# Sensoray_Breakout.net
KiCad netlist of a schematic drawn in EAGLE
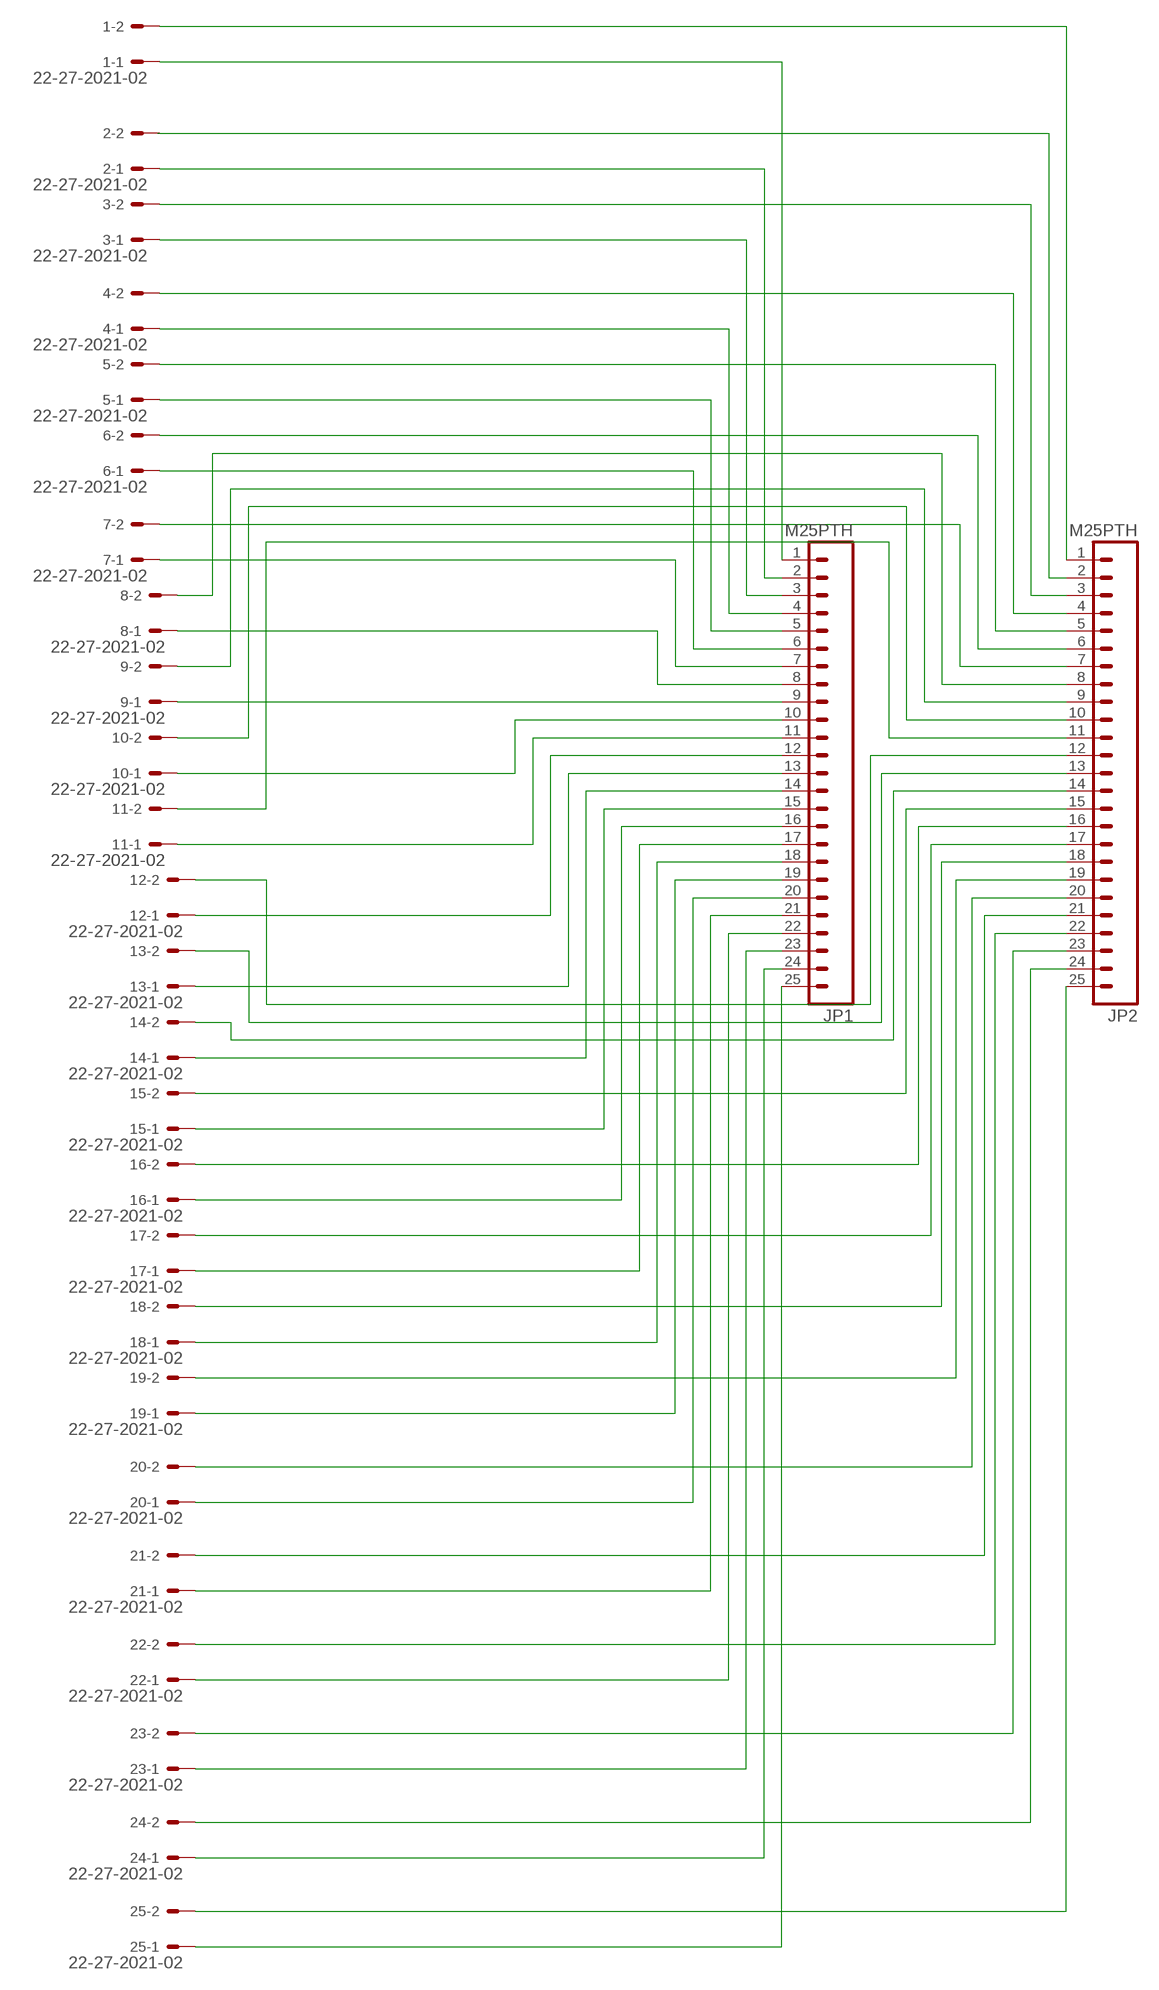
[diagram p0: schematic, sheet 1]

(export (version "E")
  (design (tool "Eeschema 10.0.6"))
  (components
    (comp (ref "1")
      (value "22-27-2021-02")
      (footprint "eagle-import:6410-02")
      (libsource (lib "eagle-import") (part "22-?-0227-2021"))
    )
    (comp (ref "2")
      (value "22-27-2021-02")
      (footprint "eagle-import:6410-02")
      (libsource (lib "eagle-import") (part "22-?-0227-2021"))
    )
    (comp (ref "3")
      (value "22-27-2021-02")
      (footprint "eagle-import:6410-02")
      (libsource (lib "eagle-import") (part "22-?-0227-2021"))
    )
    (comp (ref "4")
      (value "22-27-2021-02")
      (footprint "eagle-import:6410-02")
      (libsource (lib "eagle-import") (part "22-?-0227-2021"))
    )
    (comp (ref "5")
      (value "22-27-2021-02")
      (footprint "eagle-import:6410-02")
      (libsource (lib "eagle-import") (part "22-?-0227-2021"))
    )
    (comp (ref "6")
      (value "22-27-2021-02")
      (footprint "eagle-import:6410-02")
      (libsource (lib "eagle-import") (part "22-?-0227-2021"))
    )
    (comp (ref "7")
      (value "22-27-2021-02")
      (footprint "eagle-import:6410-02")
      (libsource (lib "eagle-import") (part "22-?-0227-2021"))
    )
    (comp (ref "8")
      (value "22-27-2021-02")
      (footprint "eagle-import:6410-02")
      (libsource (lib "eagle-import") (part "22-?-0227-2021"))
    )
    (comp (ref "9")
      (value "22-27-2021-02")
      (footprint "eagle-import:6410-02")
      (libsource (lib "eagle-import") (part "22-?-0227-2021"))
    )
    (comp (ref "10")
      (value "22-27-2021-02")
      (footprint "eagle-import:6410-02")
      (libsource (lib "eagle-import") (part "22-?-0227-2021"))
    )
    (comp (ref "11")
      (value "22-27-2021-02")
      (footprint "eagle-import:6410-02")
      (libsource (lib "eagle-import") (part "22-?-0227-2021"))
    )
    (comp (ref "12")
      (value "22-27-2021-02")
      (footprint "eagle-import:6410-02")
      (libsource (lib "eagle-import") (part "22-?-0227-2021"))
    )
    (comp (ref "13")
      (value "22-27-2021-02")
      (footprint "eagle-import:6410-02")
      (libsource (lib "eagle-import") (part "22-?-0227-2021"))
    )
    (comp (ref "14")
      (value "22-27-2021-02")
      (footprint "eagle-import:6410-02")
      (libsource (lib "eagle-import") (part "22-?-0227-2021"))
    )
    (comp (ref "15")
      (value "22-27-2021-02")
      (footprint "eagle-import:6410-02")
      (libsource (lib "eagle-import") (part "22-?-0227-2021"))
    )
    (comp (ref "16")
      (value "22-27-2021-02")
      (footprint "eagle-import:6410-02")
      (libsource (lib "eagle-import") (part "22-?-0227-2021"))
    )
    (comp (ref "17")
      (value "22-27-2021-02")
      (footprint "eagle-import:6410-02")
      (libsource (lib "eagle-import") (part "22-?-0227-2021"))
    )
    (comp (ref "18")
      (value "22-27-2021-02")
      (footprint "eagle-import:6410-02")
      (libsource (lib "eagle-import") (part "22-?-0227-2021"))
    )
    (comp (ref "19")
      (value "22-27-2021-02")
      (footprint "eagle-import:6410-02")
      (libsource (lib "eagle-import") (part "22-?-0227-2021"))
    )
    (comp (ref "20")
      (value "22-27-2021-02")
      (footprint "eagle-import:6410-02")
      (libsource (lib "eagle-import") (part "22-?-0227-2021"))
    )
    (comp (ref "21")
      (value "22-27-2021-02")
      (footprint "eagle-import:6410-02")
      (libsource (lib "eagle-import") (part "22-?-0227-2021"))
    )
    (comp (ref "22")
      (value "22-27-2021-02")
      (footprint "eagle-import:6410-02")
      (libsource (lib "eagle-import") (part "22-?-0227-2021"))
    )
    (comp (ref "23")
      (value "22-27-2021-02")
      (footprint "eagle-import:6410-02")
      (libsource (lib "eagle-import") (part "22-?-0227-2021"))
    )
    (comp (ref "24")
      (value "22-27-2021-02")
      (footprint "eagle-import:6410-02")
      (libsource (lib "eagle-import") (part "22-?-0227-2021"))
    )
    (comp (ref "25")
      (value "22-27-2021-02")
      (footprint "eagle-import:6410-02")
      (libsource (lib "eagle-import") (part "22-?-0227-2021"))
    )
    (comp (ref "JP1")
      (value "M25PTH")
      (footprint "eagle-import:1X25")
      (libsource (lib "eagle-import") (part "M25PTH"))
    )
    (comp (ref "JP2")
      (value "M25PTH")
      (footprint "eagle-import:1X25")
      (libsource (lib "eagle-import") (part "M25PTH"))
    )
  )
  (nets
    (net (code "1") (name "Net-(1A-S)") (class "Default")
      (node (ref "1") (pin "1") (pinfunction "S_1") (pintype "passive"))
      (node (ref "JP1") (pin "1") (pinfunction "1_1") (pintype "passive"))
    )
    (net (code "2") (name "Net-(1B-S)") (class "Default")
      (node (ref "1") (pin "2") (pinfunction "S_2") (pintype "passive"))
      (node (ref "JP2") (pin "1") (pinfunction "1_1") (pintype "passive"))
    )
    (net (code "3") (name "Net-(2A-S)") (class "Default")
      (node (ref "2") (pin "1") (pinfunction "S_1") (pintype "passive"))
      (node (ref "JP1") (pin "2") (pinfunction "2_2") (pintype "passive"))
    )
    (net (code "4") (name "Net-(2B-S)") (class "Default")
      (node (ref "2") (pin "2") (pinfunction "S_2") (pintype "passive"))
      (node (ref "JP2") (pin "2") (pinfunction "2_2") (pintype "passive"))
    )
    (net (code "5") (name "Net-(3A-S)") (class "Default")
      (node (ref "3") (pin "1") (pinfunction "S_1") (pintype "passive"))
      (node (ref "JP1") (pin "3") (pinfunction "3_3") (pintype "passive"))
    )
    (net (code "6") (name "Net-(3B-S)") (class "Default")
      (node (ref "3") (pin "2") (pinfunction "S_2") (pintype "passive"))
      (node (ref "JP2") (pin "3") (pinfunction "3_3") (pintype "passive"))
    )
    (net (code "7") (name "Net-(4A-S)") (class "Default")
      (node (ref "4") (pin "1") (pinfunction "S_1") (pintype "passive"))
      (node (ref "JP1") (pin "4") (pinfunction "4_4") (pintype "passive"))
    )
    (net (code "8") (name "Net-(4B-S)") (class "Default")
      (node (ref "4") (pin "2") (pinfunction "S_2") (pintype "passive"))
      (node (ref "JP2") (pin "4") (pinfunction "4_4") (pintype "passive"))
    )
    (net (code "9") (name "Net-(5A-S)") (class "Default")
      (node (ref "5") (pin "1") (pinfunction "S_1") (pintype "passive"))
      (node (ref "JP1") (pin "5") (pinfunction "5_5") (pintype "passive"))
    )
    (net (code "10") (name "Net-(5B-S)") (class "Default")
      (node (ref "5") (pin "2") (pinfunction "S_2") (pintype "passive"))
      (node (ref "JP2") (pin "5") (pinfunction "5_5") (pintype "passive"))
    )
    (net (code "11") (name "Net-(6A-S)") (class "Default")
      (node (ref "6") (pin "1") (pinfunction "S_1") (pintype "passive"))
      (node (ref "JP1") (pin "6") (pinfunction "6_6") (pintype "passive"))
    )
    (net (code "12") (name "Net-(6B-S)") (class "Default")
      (node (ref "6") (pin "2") (pinfunction "S_2") (pintype "passive"))
      (node (ref "JP2") (pin "6") (pinfunction "6_6") (pintype "passive"))
    )
    (net (code "13") (name "Net-(7A-S)") (class "Default")
      (node (ref "7") (pin "1") (pinfunction "S_1") (pintype "passive"))
      (node (ref "JP1") (pin "7") (pinfunction "7_7") (pintype "passive"))
    )
    (net (code "14") (name "Net-(7B-S)") (class "Default")
      (node (ref "7") (pin "2") (pinfunction "S_2") (pintype "passive"))
      (node (ref "JP2") (pin "7") (pinfunction "7_7") (pintype "passive"))
    )
    (net (code "15") (name "Net-(8A-S)") (class "Default")
      (node (ref "8") (pin "1") (pinfunction "S_1") (pintype "passive"))
      (node (ref "JP1") (pin "8") (pinfunction "8_8") (pintype "passive"))
    )
    (net (code "16") (name "Net-(8B-S)") (class "Default")
      (node (ref "8") (pin "2") (pinfunction "S_2") (pintype "passive"))
      (node (ref "JP2") (pin "8") (pinfunction "8_8") (pintype "passive"))
    )
    (net (code "17") (name "Net-(9A-S)") (class "Default")
      (node (ref "9") (pin "1") (pinfunction "S_1") (pintype "passive"))
      (node (ref "JP1") (pin "9") (pinfunction "9_9") (pintype "passive"))
    )
    (net (code "18") (name "Net-(9B-S)") (class "Default")
      (node (ref "9") (pin "2") (pinfunction "S_2") (pintype "passive"))
      (node (ref "JP2") (pin "9") (pinfunction "9_9") (pintype "passive"))
    )
    (net (code "19") (name "Net-(10A-S)") (class "Default")
      (node (ref "10") (pin "1") (pinfunction "S_1") (pintype "passive"))
      (node (ref "JP1") (pin "10") (pinfunction "10_10") (pintype "passive"))
    )
    (net (code "20") (name "Net-(10B-S)") (class "Default")
      (node (ref "10") (pin "2") (pinfunction "S_2") (pintype "passive"))
      (node (ref "JP2") (pin "10") (pinfunction "10_10") (pintype "passive"))
    )
    (net (code "21") (name "Net-(11A-S)") (class "Default")
      (node (ref "11") (pin "1") (pinfunction "S_1") (pintype "passive"))
      (node (ref "JP1") (pin "11") (pinfunction "11_11") (pintype "passive"))
    )
    (net (code "22") (name "Net-(11B-S)") (class "Default")
      (node (ref "11") (pin "2") (pinfunction "S_2") (pintype "passive"))
      (node (ref "JP2") (pin "11") (pinfunction "11_11") (pintype "passive"))
    )
    (net (code "23") (name "Net-(12A-S)") (class "Default")
      (node (ref "12") (pin "1") (pinfunction "S_1") (pintype "passive"))
      (node (ref "JP1") (pin "12") (pinfunction "12_12") (pintype "passive"))
    )
    (net (code "24") (name "Net-(12B-S)") (class "Default")
      (node (ref "12") (pin "2") (pinfunction "S_2") (pintype "passive"))
      (node (ref "JP2") (pin "12") (pinfunction "12_12") (pintype "passive"))
    )
    (net (code "25") (name "Net-(13A-S)") (class "Default")
      (node (ref "13") (pin "1") (pinfunction "S_1") (pintype "passive"))
      (node (ref "JP1") (pin "13") (pinfunction "13_13") (pintype "passive"))
    )
    (net (code "26") (name "Net-(13B-S)") (class "Default")
      (node (ref "13") (pin "2") (pinfunction "S_2") (pintype "passive"))
      (node (ref "JP2") (pin "13") (pinfunction "13_13") (pintype "passive"))
    )
    (net (code "27") (name "Net-(14A-S)") (class "Default")
      (node (ref "14") (pin "1") (pinfunction "S_1") (pintype "passive"))
      (node (ref "JP1") (pin "14") (pinfunction "14_14") (pintype "passive"))
    )
    (net (code "28") (name "Net-(14B-S)") (class "Default")
      (node (ref "14") (pin "2") (pinfunction "S_2") (pintype "passive"))
      (node (ref "JP2") (pin "14") (pinfunction "14_14") (pintype "passive"))
    )
    (net (code "29") (name "Net-(15A-S)") (class "Default")
      (node (ref "15") (pin "1") (pinfunction "S_1") (pintype "passive"))
      (node (ref "JP1") (pin "15") (pinfunction "15_15") (pintype "passive"))
    )
    (net (code "30") (name "Net-(15B-S)") (class "Default")
      (node (ref "15") (pin "2") (pinfunction "S_2") (pintype "passive"))
      (node (ref "JP2") (pin "15") (pinfunction "15_15") (pintype "passive"))
    )
    (net (code "31") (name "Net-(16A-S)") (class "Default")
      (node (ref "16") (pin "1") (pinfunction "S_1") (pintype "passive"))
      (node (ref "JP1") (pin "16") (pinfunction "16_16") (pintype "passive"))
    )
    (net (code "32") (name "Net-(16B-S)") (class "Default")
      (node (ref "16") (pin "2") (pinfunction "S_2") (pintype "passive"))
      (node (ref "JP2") (pin "16") (pinfunction "16_16") (pintype "passive"))
    )
    (net (code "33") (name "Net-(17A-S)") (class "Default")
      (node (ref "17") (pin "1") (pinfunction "S_1") (pintype "passive"))
      (node (ref "JP1") (pin "17") (pinfunction "17_17") (pintype "passive"))
    )
    (net (code "34") (name "Net-(17B-S)") (class "Default")
      (node (ref "17") (pin "2") (pinfunction "S_2") (pintype "passive"))
      (node (ref "JP2") (pin "17") (pinfunction "17_17") (pintype "passive"))
    )
    (net (code "35") (name "Net-(18A-S)") (class "Default")
      (node (ref "18") (pin "1") (pinfunction "S_1") (pintype "passive"))
      (node (ref "JP1") (pin "18") (pinfunction "18_18") (pintype "passive"))
    )
    (net (code "36") (name "Net-(18B-S)") (class "Default")
      (node (ref "18") (pin "2") (pinfunction "S_2") (pintype "passive"))
      (node (ref "JP2") (pin "18") (pinfunction "18_18") (pintype "passive"))
    )
    (net (code "37") (name "Net-(19A-S)") (class "Default")
      (node (ref "19") (pin "1") (pinfunction "S_1") (pintype "passive"))
      (node (ref "JP1") (pin "19") (pinfunction "19_19") (pintype "passive"))
    )
    (net (code "38") (name "Net-(19B-S)") (class "Default")
      (node (ref "19") (pin "2") (pinfunction "S_2") (pintype "passive"))
      (node (ref "JP2") (pin "19") (pinfunction "19_19") (pintype "passive"))
    )
    (net (code "39") (name "Net-(20A-S)") (class "Default")
      (node (ref "20") (pin "1") (pinfunction "S_1") (pintype "passive"))
      (node (ref "JP1") (pin "20") (pinfunction "20_20") (pintype "passive"))
    )
    (net (code "40") (name "Net-(20B-S)") (class "Default")
      (node (ref "20") (pin "2") (pinfunction "S_2") (pintype "passive"))
      (node (ref "JP2") (pin "20") (pinfunction "20_20") (pintype "passive"))
    )
    (net (code "41") (name "Net-(21A-S)") (class "Default")
      (node (ref "21") (pin "1") (pinfunction "S_1") (pintype "passive"))
      (node (ref "JP1") (pin "21") (pinfunction "21_21") (pintype "passive"))
    )
    (net (code "42") (name "Net-(21B-S)") (class "Default")
      (node (ref "21") (pin "2") (pinfunction "S_2") (pintype "passive"))
      (node (ref "JP2") (pin "21") (pinfunction "21_21") (pintype "passive"))
    )
    (net (code "43") (name "Net-(22A-S)") (class "Default")
      (node (ref "22") (pin "1") (pinfunction "S_1") (pintype "passive"))
      (node (ref "JP1") (pin "22") (pinfunction "22_22") (pintype "passive"))
    )
    (net (code "44") (name "Net-(22B-S)") (class "Default")
      (node (ref "22") (pin "2") (pinfunction "S_2") (pintype "passive"))
      (node (ref "JP2") (pin "22") (pinfunction "22_22") (pintype "passive"))
    )
    (net (code "45") (name "Net-(23A-S)") (class "Default")
      (node (ref "23") (pin "1") (pinfunction "S_1") (pintype "passive"))
      (node (ref "JP1") (pin "23") (pinfunction "23_23") (pintype "passive"))
    )
    (net (code "46") (name "Net-(23B-S)") (class "Default")
      (node (ref "23") (pin "2") (pinfunction "S_2") (pintype "passive"))
      (node (ref "JP2") (pin "23") (pinfunction "23_23") (pintype "passive"))
    )
    (net (code "47") (name "Net-(24A-S)") (class "Default")
      (node (ref "24") (pin "1") (pinfunction "S_1") (pintype "passive"))
      (node (ref "JP1") (pin "24") (pinfunction "24_24") (pintype "passive"))
    )
    (net (code "48") (name "Net-(24B-S)") (class "Default")
      (node (ref "24") (pin "2") (pinfunction "S_2") (pintype "passive"))
      (node (ref "JP2") (pin "24") (pinfunction "24_24") (pintype "passive"))
    )
    (net (code "49") (name "Net-(25A-S)") (class "Default")
      (node (ref "25") (pin "1") (pinfunction "S_1") (pintype "passive"))
      (node (ref "JP1") (pin "25") (pinfunction "25_25") (pintype "passive"))
    )
    (net (code "50") (name "Net-(25B-S)") (class "Default")
      (node (ref "25") (pin "2") (pinfunction "S_2") (pintype "passive"))
      (node (ref "JP2") (pin "25") (pinfunction "25_25") (pintype "passive"))
    )
  )
)
